# ARM2toARM3Adapter.net
KiCad netlist of a schematic drawn in Altium Designer
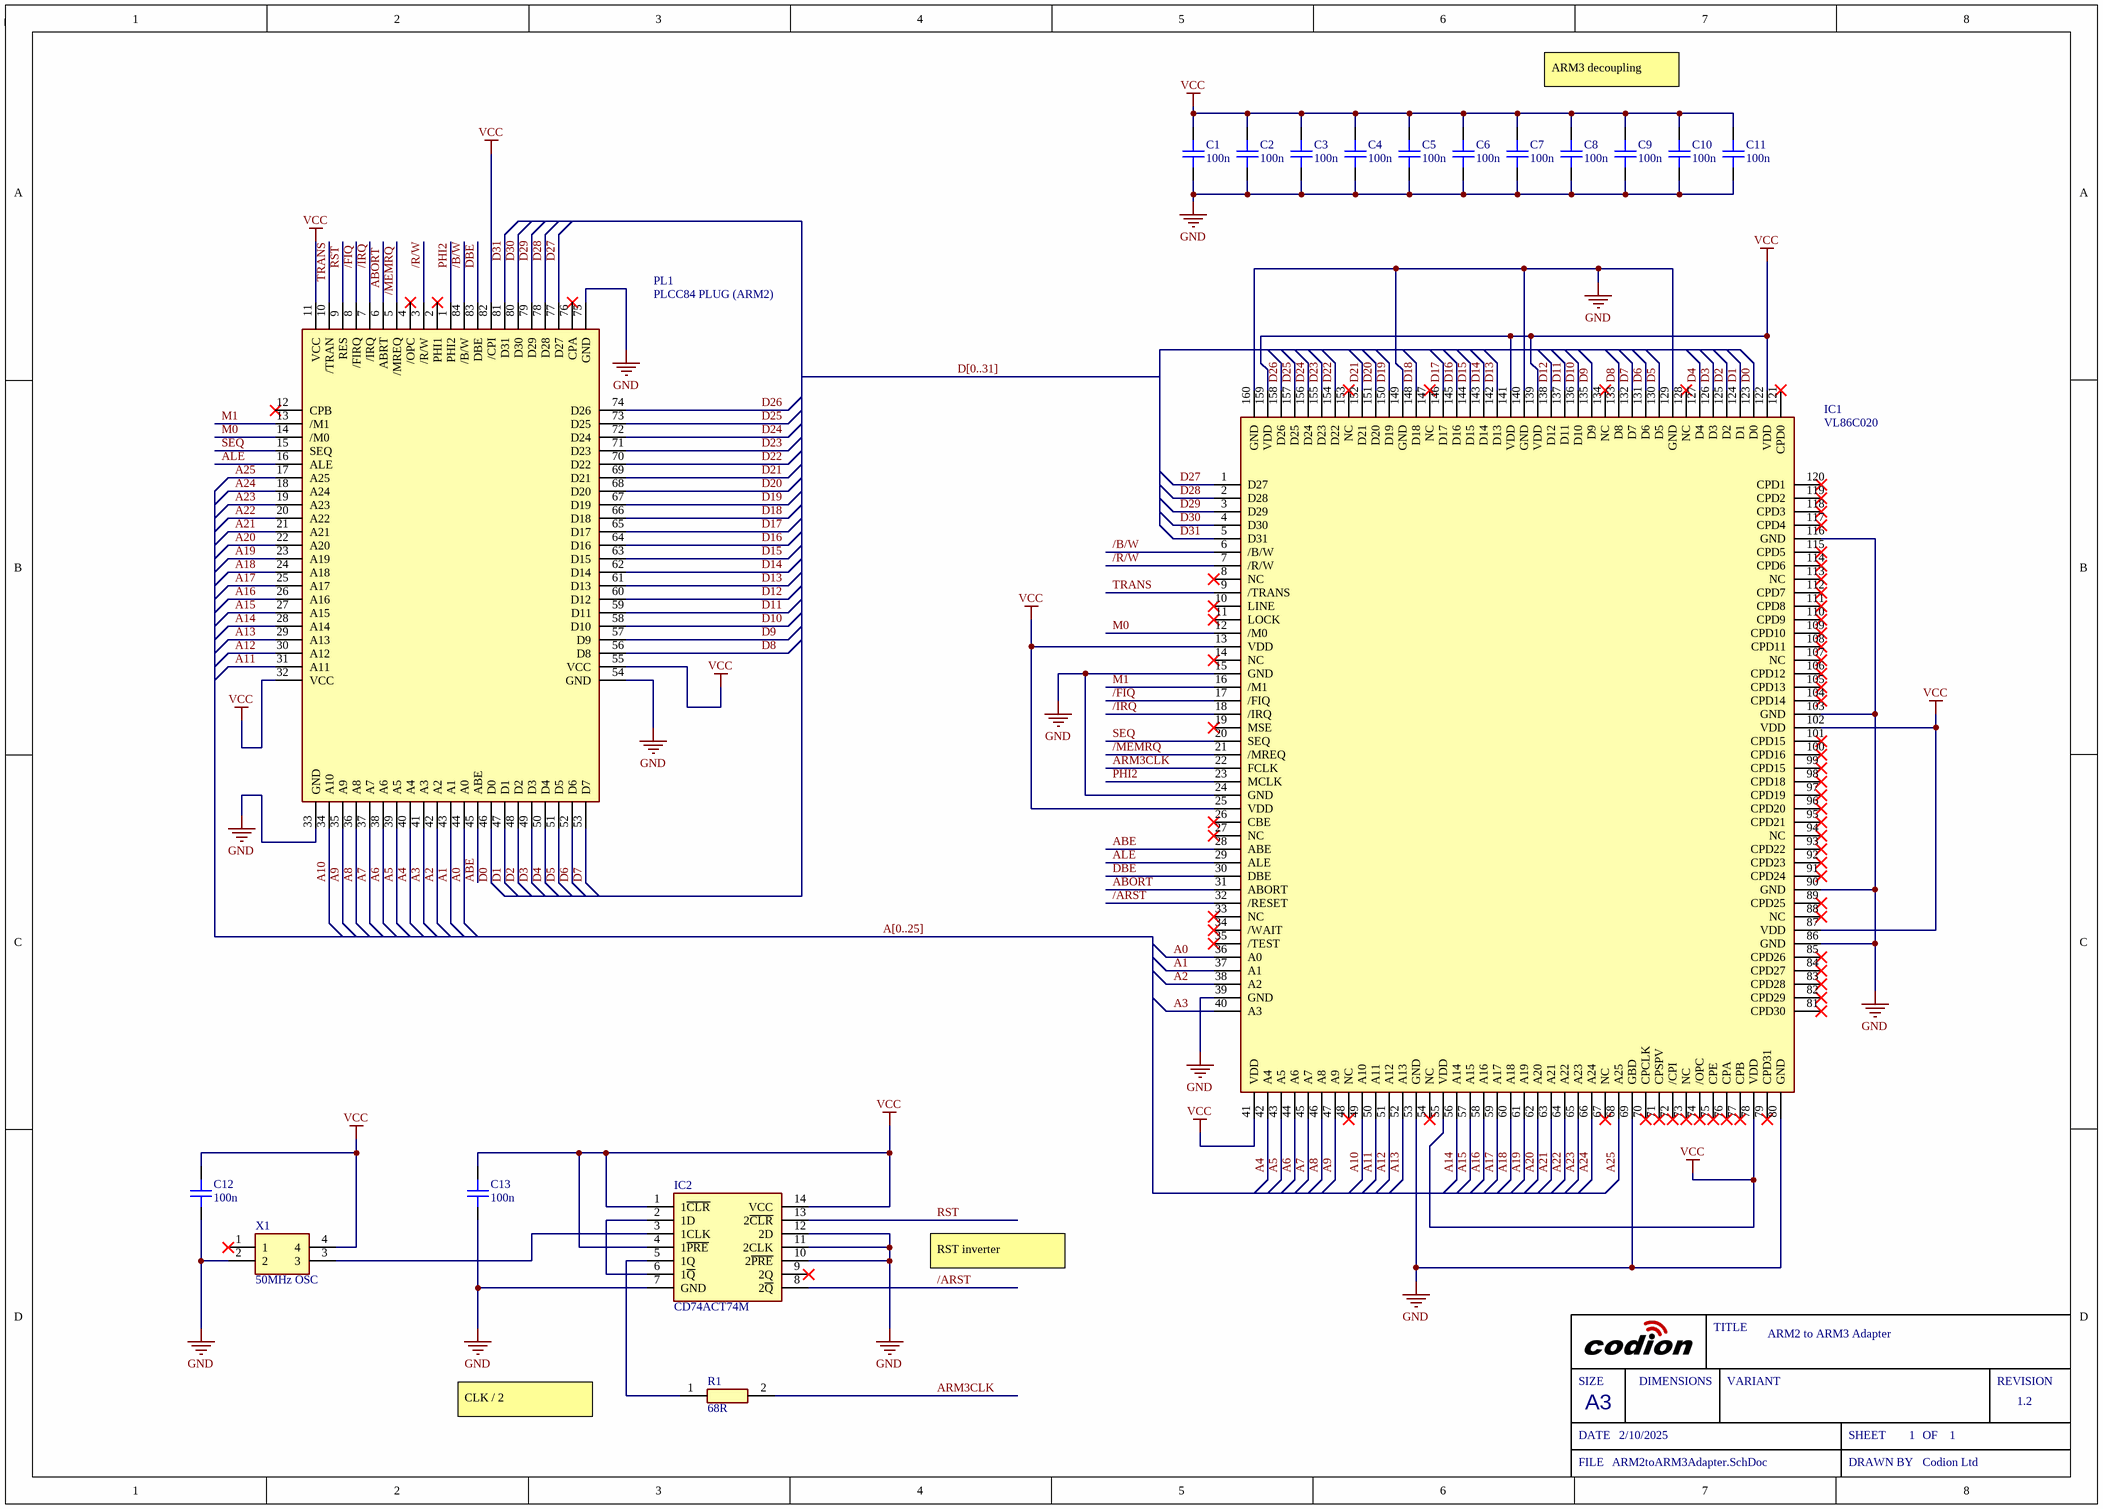
[diagram p0: ARM2toARM3Adapter.SchDoc]

(export (version "E")
  (design (tool "Eeschema 10.0.6"))
  (components
    (comp (ref "C1")
      (value "100n")
      (footprint "CAPC1608L")
      (description "CAP 100nF, 0603, 50V, X7R, 10%")
      (fields
        (field (name "DISTRIBUTOR1 PART NO") "CL10B104KB8NNNC")
        (field (name "DISTRIBUTOR2 PART NO") "311-1344-2-ND")
      )
      (libsource (lib "MCP1002_RevC") (part "CAP_100n_0603_50V_0"))
    )
    (comp (ref "C2")
      (value "100n")
      (footprint "CAPC1608L")
      (description "CAP 100nF, 0603, 50V, X7R, 10%")
      (fields
        (field (name "DISTRIBUTOR1 PART NO") "CL10B104KB8NNNC")
        (field (name "DISTRIBUTOR2 PART NO") "311-1344-2-ND")
      )
      (libsource (lib "MCP1002_RevC") (part "CAP_100n_0603_50V_0"))
    )
    (comp (ref "C3")
      (value "100n")
      (footprint "CAPC1608L")
      (description "CAP 100nF, 0603, 50V, X7R, 10%")
      (fields
        (field (name "DISTRIBUTOR1 PART NO") "CL10B104KB8NNNC")
        (field (name "DISTRIBUTOR2 PART NO") "311-1344-2-ND")
      )
      (libsource (lib "MCP1002_RevC") (part "CAP_100n_0603_50V_0"))
    )
    (comp (ref "C4")
      (value "100n")
      (footprint "CAPC1608L")
      (description "CAP 100nF, 0603, 50V, X7R, 10%")
      (fields
        (field (name "DISTRIBUTOR1 PART NO") "CL10B104KB8NNNC")
        (field (name "DISTRIBUTOR2 PART NO") "311-1344-2-ND")
      )
      (libsource (lib "MCP1002_RevC") (part "CAP_100n_0603_50V_0"))
    )
    (comp (ref "C5")
      (value "100n")
      (footprint "CAPC1608L")
      (description "CAP 100nF, 0603, 50V, X7R, 10%")
      (fields
        (field (name "DISTRIBUTOR1 PART NO") "CL10B104KB8NNNC")
        (field (name "DISTRIBUTOR2 PART NO") "311-1344-2-ND")
      )
      (libsource (lib "MCP1002_RevC") (part "CAP_100n_0603_50V_0"))
    )
    (comp (ref "C6")
      (value "100n")
      (footprint "CAPC1608L")
      (description "CAP 100nF, 0603, 50V, X7R, 10%")
      (fields
        (field (name "DISTRIBUTOR1 PART NO") "CL10B104KB8NNNC")
        (field (name "DISTRIBUTOR2 PART NO") "311-1344-2-ND")
      )
      (libsource (lib "MCP1002_RevC") (part "CAP_100n_0603_50V_0"))
    )
    (comp (ref "C7")
      (value "100n")
      (footprint "CAPC1608L")
      (description "CAP 100nF, 0603, 50V, X7R, 10%")
      (fields
        (field (name "DISTRIBUTOR1 PART NO") "CL10B104KB8NNNC")
        (field (name "DISTRIBUTOR2 PART NO") "311-1344-2-ND")
      )
      (libsource (lib "MCP1002_RevC") (part "CAP_100n_0603_50V_0"))
    )
    (comp (ref "C8")
      (value "100n")
      (footprint "CAPC1608L")
      (description "CAP 100nF, 0603, 50V, X7R, 10%")
      (fields
        (field (name "DISTRIBUTOR1 PART NO") "CL10B104KB8NNNC")
        (field (name "DISTRIBUTOR2 PART NO") "311-1344-2-ND")
      )
      (libsource (lib "MCP1002_RevC") (part "CAP_100n_0603_50V_0"))
    )
    (comp (ref "C9")
      (value "100n")
      (footprint "CAPC1608L")
      (description "CAP 100nF, 0603, 50V, X7R, 10%")
      (fields
        (field (name "DISTRIBUTOR1 PART NO") "CL10B104KB8NNNC")
        (field (name "DISTRIBUTOR2 PART NO") "311-1344-2-ND")
      )
      (libsource (lib "MCP1002_RevC") (part "CAP_100n_0603_50V_0"))
    )
    (comp (ref "C10")
      (value "100n")
      (footprint "CAPC1608L")
      (description "CAP 100nF, 0603, 50V, X7R, 10%")
      (fields
        (field (name "DISTRIBUTOR1 PART NO") "CL10B104KB8NNNC")
        (field (name "DISTRIBUTOR2 PART NO") "311-1344-2-ND")
      )
      (libsource (lib "MCP1002_RevC") (part "CAP_100n_0603_50V_0"))
    )
    (comp (ref "C11")
      (value "100n")
      (footprint "CAPC1608L")
      (description "CAP 100nF, 0603, 50V, X7R, 10%")
      (fields
        (field (name "DISTRIBUTOR1 PART NO") "CL10B104KB8NNNC")
        (field (name "DISTRIBUTOR2 PART NO") "311-1344-2-ND")
      )
      (libsource (lib "MCP1002_RevC") (part "CAP_100n_0603_50V_0"))
    )
    (comp (ref "C12")
      (value "100n")
      (footprint "CAPC1608L")
      (description "CAP 100nF, 0603, 50V, X7R, 10%")
      (fields
        (field (name "DISTRIBUTOR1 PART NO") "CL10B104KB8NNNC")
        (field (name "DISTRIBUTOR2 PART NO") "311-1344-2-ND")
      )
      (libsource (lib "MCP1002_RevC") (part "CAP_100n_0603_50V_0"))
    )
    (comp (ref "C13")
      (value "100n")
      (footprint "CAPC1608L")
      (description "CAP 100nF, 0603, 50V, X7R, 10%")
      (fields
        (field (name "DISTRIBUTOR1 PART NO") "CL10B104KB8NNNC")
        (field (name "DISTRIBUTOR2 PART NO") "311-1344-2-ND")
      )
      (libsource (lib "MCP1002_RevC") (part "CAP_100n_0603_50V_0"))
    )
    (comp (ref "IC1")
      (value "VL86C020")
      (footprint "SamacSys:QFP65P3120X3120X407-160N")
      (description "ARM3")
      (fields (field (name "MANUFACTURER_PART_NUMBER") "VL86C)20"))
      (libsource (lib "*") (part "SAA7146AH_V4,557"))
    )
    (comp (ref "IC2")
      (value "CD74ACT74M")
      (footprint "SamacSys:SOIC127P600X175-14N")
      (description "Integrated Circuit")
      (fields (field (name "MOUSER PART NUMBER") "595-CD74ACT74M"))
      (libsource (lib "*") (part "CD74ACT74M"))
    )
    (comp (ref "PL1")
      (value "PLCC84 PLUG (ARM2)")
      (footprint "PLCC84_PLUG")
      (description "PLCC84 Plug")
      (fields (field (name "MANUFACTURER_PART_NUMBER") "W9328"))
      (libsource (lib "ARM2toARM3Adapter") (part "PLCC84_PLUG_ARM2"))
    )
    (comp (ref "R1")
      (value "68R")
      (footprint "SamacSys:RESC2012X50N")
      (description "68R Resistor")
      (fields
        (field (name "MANUFACTURER_PART_NUMBER") "CRCW080568R0FKEA")
        (field (name "MOUSER PART NUMBER") "71-CRCW080568R0FKEA")
      )
      (libsource (lib "*") (part "CRCW080568R0FKEA"))
    )
    (comp (ref "X1")
      (value "50MHz OSC")
      (footprint "SamacSys:DIPS762W56P1524L1778H241Q4N")
      (fields
        (field (name "MANUFACTURER_PART_NUMBER") "1107741")
        (field (name "MOUSER PART NUMBER") "535-1107741")
      )
      (libsource (lib "*") (part "1107741"))
    )
  )
  (nets
    (net (code "1") (name "/A0") (class "Default")
      (node (ref "IC1") (pin "36") (pinfunction "A0_36") (pintype "passive"))
      (node (ref "PL1") (pin "44") (pinfunction "A0_44") (pintype "passive"))
    )
    (net (code "2") (name "/A1") (class "Default")
      (node (ref "IC1") (pin "37") (pinfunction "A1_37") (pintype "passive"))
      (node (ref "PL1") (pin "43") (pinfunction "A1_43") (pintype "passive"))
    )
    (net (code "3") (name "/A2") (class "Default")
      (node (ref "IC1") (pin "38") (pinfunction "A2_38") (pintype "passive"))
      (node (ref "PL1") (pin "42") (pinfunction "A2_42") (pintype "passive"))
    )
    (net (code "4") (name "/A3") (class "Default")
      (node (ref "IC1") (pin "40") (pinfunction "A3_40") (pintype "passive"))
      (node (ref "PL1") (pin "41") (pinfunction "A3_41") (pintype "passive"))
    )
    (net (code "5") (name "/A4") (class "Default")
      (node (ref "IC1") (pin "42") (pinfunction "A4_42") (pintype "passive"))
      (node (ref "PL1") (pin "40") (pinfunction "A4_40") (pintype "passive"))
    )
    (net (code "6") (name "/A5") (class "Default")
      (node (ref "IC1") (pin "43") (pinfunction "A5_43") (pintype "passive"))
      (node (ref "PL1") (pin "39") (pinfunction "A5_39") (pintype "passive"))
    )
    (net (code "7") (name "/A6") (class "Default")
      (node (ref "IC1") (pin "44") (pinfunction "A6_44") (pintype "passive"))
      (node (ref "PL1") (pin "38") (pinfunction "A6_38") (pintype "passive"))
    )
    (net (code "8") (name "/A7") (class "Default")
      (node (ref "IC1") (pin "45") (pinfunction "A7_45") (pintype "passive"))
      (node (ref "PL1") (pin "37") (pinfunction "A7_37") (pintype "passive"))
    )
    (net (code "9") (name "/A8") (class "Default")
      (node (ref "IC1") (pin "46") (pinfunction "A8_46") (pintype "passive"))
      (node (ref "PL1") (pin "36") (pinfunction "A8_36") (pintype "passive"))
    )
    (net (code "10") (name "/A9") (class "Default")
      (node (ref "IC1") (pin "47") (pinfunction "A9_47") (pintype "passive"))
      (node (ref "PL1") (pin "35") (pinfunction "A9_35") (pintype "passive"))
    )
    (net (code "11") (name "/A10") (class "Default")
      (node (ref "IC1") (pin "49") (pinfunction "A10_49") (pintype "passive"))
      (node (ref "PL1") (pin "34") (pinfunction "A10_34") (pintype "passive"))
    )
    (net (code "12") (name "/A11") (class "Default")
      (node (ref "IC1") (pin "50") (pinfunction "A11_50") (pintype "passive"))
      (node (ref "PL1") (pin "31") (pinfunction "A11_31") (pintype "passive"))
    )
    (net (code "13") (name "/A12") (class "Default")
      (node (ref "IC1") (pin "51") (pinfunction "A12_51") (pintype "passive"))
      (node (ref "PL1") (pin "30") (pinfunction "A12_30") (pintype "passive"))
    )
    (net (code "14") (name "/A13") (class "Default")
      (node (ref "IC1") (pin "52") (pinfunction "A13_52") (pintype "passive"))
      (node (ref "PL1") (pin "29") (pinfunction "A13_29") (pintype "passive"))
    )
    (net (code "15") (name "/A14") (class "Default")
      (node (ref "IC1") (pin "56") (pinfunction "A14_56") (pintype "passive"))
      (node (ref "PL1") (pin "28") (pinfunction "A14_28") (pintype "passive"))
    )
    (net (code "16") (name "/A15") (class "Default")
      (node (ref "IC1") (pin "57") (pinfunction "A15_57") (pintype "passive"))
      (node (ref "PL1") (pin "27") (pinfunction "A15_27") (pintype "passive"))
    )
    (net (code "17") (name "/A16") (class "Default")
      (node (ref "IC1") (pin "58") (pinfunction "A16_58") (pintype "passive"))
      (node (ref "PL1") (pin "26") (pinfunction "A16_26") (pintype "passive"))
    )
    (net (code "18") (name "/A17") (class "Default")
      (node (ref "IC1") (pin "59") (pinfunction "A17_59") (pintype "passive"))
      (node (ref "PL1") (pin "25") (pinfunction "A17_25") (pintype "passive"))
    )
    (net (code "19") (name "/A18") (class "Default")
      (node (ref "IC1") (pin "60") (pinfunction "A18_60") (pintype "passive"))
      (node (ref "PL1") (pin "24") (pinfunction "A18_24") (pintype "passive"))
    )
    (net (code "20") (name "/A19") (class "Default")
      (node (ref "IC1") (pin "61") (pinfunction "A19_61") (pintype "passive"))
      (node (ref "PL1") (pin "23") (pinfunction "A19_23") (pintype "passive"))
    )
    (net (code "21") (name "/A20") (class "Default")
      (node (ref "IC1") (pin "62") (pinfunction "A20_62") (pintype "passive"))
      (node (ref "PL1") (pin "22") (pinfunction "A20_22") (pintype "passive"))
    )
    (net (code "22") (name "/A21") (class "Default")
      (node (ref "IC1") (pin "63") (pinfunction "A21_63") (pintype "passive"))
      (node (ref "PL1") (pin "21") (pinfunction "A21_21") (pintype "passive"))
    )
    (net (code "23") (name "/A22") (class "Default")
      (node (ref "IC1") (pin "64") (pinfunction "A22_64") (pintype "passive"))
      (node (ref "PL1") (pin "20") (pinfunction "A22_20") (pintype "passive"))
    )
    (net (code "24") (name "/A23") (class "Default")
      (node (ref "IC1") (pin "65") (pinfunction "A23_65") (pintype "passive"))
      (node (ref "PL1") (pin "19") (pinfunction "A23_19") (pintype "passive"))
    )
    (net (code "25") (name "/A24") (class "Default")
      (node (ref "IC1") (pin "66") (pinfunction "A24_66") (pintype "passive"))
      (node (ref "PL1") (pin "18") (pinfunction "A24_18") (pintype "passive"))
    )
    (net (code "26") (name "/A25") (class "Default")
      (node (ref "IC1") (pin "68") (pinfunction "A25_68") (pintype "passive"))
      (node (ref "PL1") (pin "17") (pinfunction "A25_17") (pintype "passive"))
    )
    (net (code "27") (name "/ABE") (class "Default")
      (node (ref "IC1") (pin "28") (pinfunction "ABE_28") (pintype "passive"))
      (node (ref "PL1") (pin "45") (pinfunction "ABE_45") (pintype "passive"))
    )
    (net (code "28") (name "/ABORT") (class "Default")
      (node (ref "IC1") (pin "31") (pinfunction "ABORT_31") (pintype "passive"))
      (node (ref "PL1") (pin "6") (pinfunction "ABRT_6") (pintype "passive"))
    )
    (net (code "29") (name "/ALE") (class "Default")
      (node (ref "IC1") (pin "29") (pinfunction "ALE_29") (pintype "passive"))
      (node (ref "PL1") (pin "16") (pinfunction "ALE_16") (pintype "passive"))
    )
    (net (code "30") (name "/ARM3CLK") (class "Default")
      (node (ref "IC1") (pin "22") (pinfunction "FCLK_22") (pintype "passive"))
      (node (ref "R1") (pin "2") (pinfunction "2_2") (pintype "passive"))
    )
    (net (code "32") (name "/D0") (class "Default")
      (node (ref "IC1") (pin "123") (pinfunction "D0_123") (pintype "passive"))
      (node (ref "PL1") (pin "46") (pinfunction "D0_46") (pintype "passive"))
    )
    (net (code "33") (name "/D1") (class "Default")
      (node (ref "IC1") (pin "124") (pinfunction "D1_124") (pintype "passive"))
      (node (ref "PL1") (pin "47") (pinfunction "D1_47") (pintype "passive"))
    )
    (net (code "34") (name "/D2") (class "Default")
      (node (ref "IC1") (pin "125") (pinfunction "D2_125") (pintype "passive"))
      (node (ref "PL1") (pin "48") (pinfunction "D2_48") (pintype "passive"))
    )
    (net (code "35") (name "/D3") (class "Default")
      (node (ref "IC1") (pin "126") (pinfunction "D3_126") (pintype "passive"))
      (node (ref "PL1") (pin "49") (pinfunction "D3_49") (pintype "passive"))
    )
    (net (code "36") (name "/D4") (class "Default")
      (node (ref "IC1") (pin "127") (pinfunction "D4_127") (pintype "passive"))
      (node (ref "PL1") (pin "50") (pinfunction "D4_50") (pintype "passive"))
    )
    (net (code "37") (name "/D5") (class "Default")
      (node (ref "IC1") (pin "130") (pinfunction "D5_130") (pintype "passive"))
      (node (ref "PL1") (pin "51") (pinfunction "D5_51") (pintype "passive"))
    )
    (net (code "38") (name "/D6") (class "Default")
      (node (ref "IC1") (pin "131") (pinfunction "D6_131") (pintype "passive"))
      (node (ref "PL1") (pin "52") (pinfunction "D6_52") (pintype "passive"))
    )
    (net (code "39") (name "/D7") (class "Default")
      (node (ref "IC1") (pin "132") (pinfunction "D7_132") (pintype "passive"))
      (node (ref "PL1") (pin "53") (pinfunction "D7_53") (pintype "passive"))
    )
    (net (code "40") (name "/D8") (class "Default")
      (node (ref "IC1") (pin "133") (pinfunction "D8_133") (pintype "passive"))
      (node (ref "PL1") (pin "56") (pinfunction "D8_56") (pintype "passive"))
    )
    (net (code "41") (name "/D9") (class "Default")
      (node (ref "IC1") (pin "135") (pinfunction "D9_135") (pintype "passive"))
      (node (ref "PL1") (pin "57") (pinfunction "D9_57") (pintype "passive"))
    )
    (net (code "42") (name "/D10") (class "Default")
      (node (ref "IC1") (pin "136") (pinfunction "D10_136") (pintype "passive"))
      (node (ref "PL1") (pin "58") (pinfunction "D10_58") (pintype "passive"))
    )
    (net (code "43") (name "/D11") (class "Default")
      (node (ref "IC1") (pin "137") (pinfunction "D11_137") (pintype "passive"))
      (node (ref "PL1") (pin "59") (pinfunction "D11_59") (pintype "passive"))
    )
    (net (code "44") (name "/D12") (class "Default")
      (node (ref "IC1") (pin "138") (pinfunction "D12_138") (pintype "passive"))
      (node (ref "PL1") (pin "60") (pinfunction "D12_60") (pintype "passive"))
    )
    (net (code "45") (name "/D13") (class "Default")
      (node (ref "IC1") (pin "142") (pinfunction "D13_142") (pintype "passive"))
      (node (ref "PL1") (pin "61") (pinfunction "D13_61") (pintype "passive"))
    )
    (net (code "46") (name "/D14") (class "Default")
      (node (ref "IC1") (pin "143") (pinfunction "D14_143") (pintype "passive"))
      (node (ref "PL1") (pin "62") (pinfunction "D14_62") (pintype "passive"))
    )
    (net (code "47") (name "/D15") (class "Default")
      (node (ref "IC1") (pin "144") (pinfunction "D15_144") (pintype "passive"))
      (node (ref "PL1") (pin "63") (pinfunction "D15_63") (pintype "passive"))
    )
    (net (code "48") (name "/D16") (class "Default")
      (node (ref "IC1") (pin "145") (pinfunction "D16_145") (pintype "passive"))
      (node (ref "PL1") (pin "64") (pinfunction "D16_64") (pintype "passive"))
    )
    (net (code "49") (name "/D17") (class "Default")
      (node (ref "IC1") (pin "146") (pinfunction "D17_146") (pintype "passive"))
      (node (ref "PL1") (pin "65") (pinfunction "D17_65") (pintype "passive"))
    )
    (net (code "50") (name "/D18") (class "Default")
      (node (ref "IC1") (pin "148") (pinfunction "D18_148") (pintype "passive"))
      (node (ref "PL1") (pin "66") (pinfunction "D18_66") (pintype "passive"))
    )
    (net (code "51") (name "/D19") (class "Default")
      (node (ref "IC1") (pin "150") (pinfunction "D19_150") (pintype "passive"))
      (node (ref "PL1") (pin "67") (pinfunction "D19_67") (pintype "passive"))
    )
    (net (code "52") (name "/D20") (class "Default")
      (node (ref "IC1") (pin "151") (pinfunction "D20_151") (pintype "passive"))
      (node (ref "PL1") (pin "68") (pinfunction "D20_68") (pintype "passive"))
    )
    (net (code "53") (name "/D21") (class "Default")
      (node (ref "IC1") (pin "152") (pinfunction "D21_152") (pintype "passive"))
      (node (ref "PL1") (pin "69") (pinfunction "D21_69") (pintype "passive"))
    )
    (net (code "54") (name "/D22") (class "Default")
      (node (ref "IC1") (pin "154") (pinfunction "D22_154") (pintype "passive"))
      (node (ref "PL1") (pin "70") (pinfunction "D22_70") (pintype "passive"))
    )
    (net (code "55") (name "/D23") (class "Default")
      (node (ref "IC1") (pin "155") (pinfunction "D23_155") (pintype "passive"))
      (node (ref "PL1") (pin "71") (pinfunction "D23_71") (pintype "passive"))
    )
    (net (code "56") (name "/D24") (class "Default")
      (node (ref "IC1") (pin "156") (pinfunction "D24_156") (pintype "passive"))
      (node (ref "PL1") (pin "72") (pinfunction "D24_72") (pintype "passive"))
    )
    (net (code "57") (name "/D25") (class "Default")
      (node (ref "IC1") (pin "157") (pinfunction "D25_157") (pintype "passive"))
      (node (ref "PL1") (pin "73") (pinfunction "D25_73") (pintype "passive"))
    )
    (net (code "58") (name "/D26") (class "Default")
      (node (ref "IC1") (pin "158") (pinfunction "D26_158") (pintype "passive"))
      (node (ref "PL1") (pin "74") (pinfunction "D26_74") (pintype "passive"))
    )
    (net (code "59") (name "/D27") (class "Default")
      (node (ref "IC1") (pin "1") (pinfunction "D27_1") (pintype "passive"))
      (node (ref "PL1") (pin "77") (pinfunction "D27_77") (pintype "passive"))
    )
    (net (code "60") (name "/D28") (class "Default")
      (node (ref "IC1") (pin "2") (pinfunction "D28_2") (pintype "passive"))
      (node (ref "PL1") (pin "78") (pinfunction "D28_78") (pintype "passive"))
    )
    (net (code "61") (name "/D29") (class "Default")
      (node (ref "IC1") (pin "3") (pinfunction "D29_3") (pintype "passive"))
      (node (ref "PL1") (pin "79") (pinfunction "D29_79") (pintype "passive"))
    )
    (net (code "62") (name "/D30") (class "Default")
      (node (ref "IC1") (pin "4") (pinfunction "D30_4") (pintype "passive"))
      (node (ref "PL1") (pin "80") (pinfunction "D30_80") (pintype "passive"))
    )
    (net (code "63") (name "/D31") (class "Default")
      (node (ref "IC1") (pin "5") (pinfunction "D31_5") (pintype "passive"))
      (node (ref "PL1") (pin "81") (pinfunction "D31_81") (pintype "passive"))
    )
    (net (code "64") (name "/DBE") (class "Default")
      (node (ref "IC1") (pin "30") (pinfunction "DBE_30") (pintype "passive"))
      (node (ref "PL1") (pin "83") (pinfunction "DBE_83") (pintype "passive"))
    )
    (net (code "66") (name "/M0") (class "Default")
      (node (ref "IC1") (pin "12") (pinfunction "/M0_12") (pintype "passive"))
      (node (ref "PL1") (pin "14") (pinfunction "/M0_14") (pintype "passive"))
    )
    (net (code "67") (name "/M1") (class "Default")
      (node (ref "IC1") (pin "16") (pinfunction "/M1_16") (pintype "passive"))
      (node (ref "PL1") (pin "13") (pinfunction "/M1_13") (pintype "passive"))
    )
    (net (code "68") (name "/PHI2") (class "Default")
      (node (ref "IC1") (pin "23") (pinfunction "MCLK_23") (pintype "passive"))
      (node (ref "PL1") (pin "1") (pinfunction "PHI2_1") (pintype "passive"))
    )
    (net (code "69") (name "/RST") (class "Default")
      (node (ref "IC2") (pin "13") (pinfunction "2~{CLR}_13") (pintype "passive"))
      (node (ref "PL1") (pin "9") (pinfunction "RES_9") (pintype "passive"))
    )
    (net (code "70") (name "/SEQ") (class "Default")
      (node (ref "IC1") (pin "20") (pinfunction "SEQ_20") (pintype "passive"))
      (node (ref "PL1") (pin "15") (pinfunction "SEQ_15") (pintype "passive"))
    )
    (net (code "71") (name "/TRANS") (class "Default")
      (node (ref "IC1") (pin "9") (pinfunction "/TRANS_9") (pintype "passive"))
      (node (ref "PL1") (pin "10") (pinfunction "/TRAN_10") (pintype "passive"))
    )
    (net (code "72") (name "/{slash}ARST") (class "Default")
      (node (ref "IC1") (pin "32") (pinfunction "/RESET_32") (pintype "passive"))
      (node (ref "IC2") (pin "8") (pinfunction "2~{Q}_8") (pintype "passive"))
    )
    (net (code "73") (name "/{slash}B{slash}W") (class "Default")
      (node (ref "IC1") (pin "6") (pinfunction "/B/W_6") (pintype "passive"))
      (node (ref "PL1") (pin "84") (pinfunction "/B/W_84") (pintype "passive"))
    )
    (net (code "74") (name "/{slash}FIQ") (class "Default")
      (node (ref "IC1") (pin "17") (pinfunction "/FIQ_17") (pintype "passive"))
      (node (ref "PL1") (pin "8") (pinfunction "/FIRQ_8") (pintype "passive"))
    )
    (net (code "75") (name "/{slash}IRQ") (class "Default")
      (node (ref "IC1") (pin "18") (pinfunction "/IRQ_18") (pintype "passive"))
      (node (ref "PL1") (pin "7") (pinfunction "/IRQ_7") (pintype "passive"))
    )
    (net (code "76") (name "/{slash}MEMRQ") (class "Default")
      (node (ref "IC1") (pin "21") (pinfunction "/MREQ_21") (pintype "passive"))
      (node (ref "PL1") (pin "5") (pinfunction "/MREQ_5") (pintype "passive"))
    )
    (net (code "77") (name "/{slash}R{slash}W") (class "Default")
      (node (ref "IC1") (pin "7") (pinfunction "/R/W_7") (pintype "passive"))
      (node (ref "PL1") (pin "3") (pinfunction "/R/W_3") (pintype "passive"))
    )
    (net (code "78") (name "GND") (class "Default")
      (node (ref "C1") (pin "1") (pintype "passive"))
      (node (ref "C10") (pin "1") (pintype "passive"))
      (node (ref "C11") (pin "1") (pintype "passive"))
      (node (ref "C12") (pin "1") (pintype "passive"))
      (node (ref "C13") (pin "1") (pintype "passive"))
      (node (ref "C2") (pin "1") (pintype "passive"))
      (node (ref "C3") (pin "1") (pintype "passive"))
      (node (ref "C4") (pin "1") (pintype "passive"))
      (node (ref "C5") (pin "1") (pintype "passive"))
      (node (ref "C6") (pin "1") (pintype "passive"))
      (node (ref "C7") (pin "1") (pintype "passive"))
      (node (ref "C8") (pin "1") (pintype "passive"))
      (node (ref "C9") (pin "1") (pintype "passive"))
      (node (ref "IC1") (pin "103") (pinfunction "GND_103") (pintype "passive"))
      (node (ref "IC1") (pin "116") (pinfunction "GND_116") (pintype "passive"))
      (node (ref "IC1") (pin "129") (pinfunction "GND_129") (pintype "passive"))
      (node (ref "IC1") (pin "140") (pinfunction "GND_140") (pintype "passive"))
      (node (ref "IC1") (pin "149") (pinfunction "GND_149") (pintype "passive"))
      (node (ref "IC1") (pin "15") (pinfunction "GND_15") (pintype "passive"))
      (node (ref "IC1") (pin "160") (pinfunction "GND_160") (pintype "passive"))
      (node (ref "IC1") (pin "24") (pinfunction "GND_24") (pintype "passive"))
      (node (ref "IC1") (pin "39") (pinfunction "GND_39") (pintype "passive"))
      (node (ref "IC1") (pin "53") (pinfunction "GND_53") (pintype "passive"))
      (node (ref "IC1") (pin "69") (pinfunction "GBD_69") (pintype "passive"))
      (node (ref "IC1") (pin "80") (pinfunction "GND_80") (pintype "passive"))
      (node (ref "IC1") (pin "86") (pinfunction "GND_86") (pintype "passive"))
      (node (ref "IC1") (pin "90") (pinfunction "GND_90") (pintype "passive"))
      (node (ref "IC2") (pin "10") (pinfunction "2~{PRE}_10") (pintype "passive"))
      (node (ref "IC2") (pin "11") (pinfunction "2CLK_11") (pintype "passive"))
      (node (ref "IC2") (pin "12") (pinfunction "2D_12") (pintype "passive"))
      (node (ref "IC2") (pin "7") (pinfunction "GND_7") (pintype "passive"))
      (node (ref "PL1") (pin "33") (pinfunction "GND_33") (pintype "passive"))
      (node (ref "PL1") (pin "54") (pinfunction "GND_54") (pintype "passive"))
      (node (ref "PL1") (pin "75") (pinfunction "GND_75") (pintype "passive"))
      (node (ref "X1") (pin "2") (pinfunction "2_2") (pintype "passive"))
    )
    (net (code "79") (name "Net-(IC2-1CLK)") (class "Default")
      (node (ref "IC2") (pin "3") (pinfunction "1CLK_3") (pintype "passive"))
      (node (ref "X1") (pin "3") (pinfunction "3_3") (pintype "passive"))
    )
    (net (code "80") (name "Net-(IC2-1D)") (class "Default")
      (node (ref "IC2") (pin "2") (pinfunction "1D_2") (pintype "passive"))
      (node (ref "IC2") (pin "6") (pinfunction "1~{Q}_6") (pintype "passive"))
    )
    (net (code "81") (name "Net-(IC2-1Q)") (class "Default")
      (node (ref "IC2") (pin "5") (pinfunction "1Q_5") (pintype "passive"))
      (node (ref "R1") (pin "1") (pinfunction "1_1") (pintype "passive"))
    )
    (net (code "82") (name "VCC") (class "Default")
      (node (ref "C1") (pin "2") (pintype "passive"))
      (node (ref "C10") (pin "2") (pintype "passive"))
      (node (ref "C11") (pin "2") (pintype "passive"))
      (node (ref "C12") (pin "2") (pintype "passive"))
      (node (ref "C13") (pin "2") (pintype "passive"))
      (node (ref "C2") (pin "2") (pintype "passive"))
      (node (ref "C3") (pin "2") (pintype "passive"))
      (node (ref "C4") (pin "2") (pintype "passive"))
      (node (ref "C5") (pin "2") (pintype "passive"))
      (node (ref "C6") (pin "2") (pintype "passive"))
      (node (ref "C7") (pin "2") (pintype "passive"))
      (node (ref "C8") (pin "2") (pintype "passive"))
      (node (ref "C9") (pin "2") (pintype "passive"))
      (node (ref "IC1") (pin "102") (pinfunction "VDD_102") (pintype "passive"))
      (node (ref "IC1") (pin "122") (pinfunction "VDD_122") (pintype "passive"))
      (node (ref "IC1") (pin "13") (pinfunction "VDD_13") (pintype "passive"))
      (node (ref "IC1") (pin "139") (pinfunction "VDD_139") (pintype "passive"))
      (node (ref "IC1") (pin "141") (pinfunction "VDD_141") (pintype "passive"))
      (node (ref "IC1") (pin "159") (pinfunction "VDD_159") (pintype "passive"))
      (node (ref "IC1") (pin "25") (pinfunction "VDD_25") (pintype "passive"))
      (node (ref "IC1") (pin "41") (pinfunction "VDD_41") (pintype "passive"))
      (node (ref "IC1") (pin "55") (pinfunction "VDD_55") (pintype "passive"))
      (node (ref "IC1") (pin "78") (pinfunction "VDD_78") (pintype "passive"))
      (node (ref "IC1") (pin "87") (pinfunction "VDD_87") (pintype "passive"))
      (node (ref "IC2") (pin "1") (pinfunction "1~{CLR}_1") (pintype "passive"))
      (node (ref "IC2") (pin "14") (pinfunction "VCC_14") (pintype "passive"))
      (node (ref "IC2") (pin "4") (pinfunction "1~{PRE}_4") (pintype "passive"))
      (node (ref "PL1") (pin "11") (pinfunction "VCC_11") (pintype "passive"))
      (node (ref "PL1") (pin "32") (pinfunction "VCC_32") (pintype "passive"))
      (node (ref "PL1") (pin "55") (pinfunction "VCC_55") (pintype "passive"))
      (node (ref "PL1") (pin "82") (pinfunction "/CPI_82") (pintype "passive"))
      (node (ref "X1") (pin "4") (pinfunction "4_4") (pintype "passive"))
    )
    (net (code "83") (name "unconnected-(IC1-CBE-Pad26)") (class "Default")
      (node (ref "IC1") (pin "26") (pinfunction "CBE_26") (pintype "passive+no_connect"))
    )
    (net (code "84") (name "unconnected-(IC1-CPA-Pad76)") (class "Default")
      (node (ref "IC1") (pin "76") (pinfunction "CPA_76") (pintype "passive+no_connect"))
    )
    (net (code "85") (name "unconnected-(IC1-CPB-Pad77)") (class "Default")
      (node (ref "IC1") (pin "77") (pinfunction "CPB_77") (pintype "passive+no_connect"))
    )
    (net (code "86") (name "unconnected-(IC1-CPCLK-Pad70)") (class "Default")
      (node (ref "IC1") (pin "70") (pinfunction "CPCLK_70") (pintype "passive+no_connect"))
    )
    (net (code "87") (name "unconnected-(IC1-CPD0-Pad121)") (class "Default")
      (node (ref "IC1") (pin "121") (pinfunction "CPD0_121") (pintype "passive+no_connect"))
    )
    (net (code "88") (name "unconnected-(IC1-CPD1-Pad120)") (class "Default")
      (node (ref "IC1") (pin "120") (pinfunction "CPD1_120") (pintype "passive+no_connect"))
    )
    (net (code "89") (name "unconnected-(IC1-CPD2-Pad119)") (class "Default")
      (node (ref "IC1") (pin "119") (pinfunction "CPD2_119") (pintype "passive+no_connect"))
    )
    (net (code "90") (name "unconnected-(IC1-CPD3-Pad118)") (class "Default")
      (node (ref "IC1") (pin "118") (pinfunction "CPD3_118") (pintype "passive+no_connect"))
    )
    (net (code "91") (name "unconnected-(IC1-CPD4-Pad117)") (class "Default")
      (node (ref "IC1") (pin "117") (pinfunction "CPD4_117") (pintype "passive+no_connect"))
    )
    (net (code "92") (name "unconnected-(IC1-CPD5-Pad115)") (class "Default")
      (node (ref "IC1") (pin "115") (pinfunction "CPD5_115") (pintype "passive+no_connect"))
    )
    (net (code "93") (name "unconnected-(IC1-CPD6-Pad114)") (class "Default")
      (node (ref "IC1") (pin "114") (pinfunction "CPD6_114") (pintype "passive+no_connect"))
    )
    (net (code "94") (name "unconnected-(IC1-CPD7-Pad112)") (class "Default")
      (node (ref "IC1") (pin "112") (pinfunction "CPD7_112") (pintype "passive+no_connect"))
    )
    (net (code "95") (name "unconnected-(IC1-CPD8-Pad111)") (class "Default")
      (node (ref "IC1") (pin "111") (pinfunction "CPD8_111") (pintype "passive+no_connect"))
    )
    (net (code "96") (name "unconnected-(IC1-CPD9-Pad110)") (class "Default")
      (node (ref "IC1") (pin "110") (pinfunction "CPD9_110") (pintype "passive+no_connect"))
    )
    (net (code "97") (name "unconnected-(IC1-CPD10-Pad109)") (class "Default")
      (node (ref "IC1") (pin "109") (pinfunction "CPD10_109") (pintype "passive+no_connect"))
    )
    (net (code "98") (name "unconnected-(IC1-CPD11-Pad108)") (class "Default")
      (node (ref "IC1") (pin "108") (pinfunction "CPD11_108") (pintype "passive+no_connect"))
    )
    (net (code "99") (name "unconnected-(IC1-CPD12-Pad106)") (class "Default")
      (node (ref "IC1") (pin "106") (pinfunction "CPD12_106") (pintype "passive+no_connect"))
    )
    (net (code "100") (name "unconnected-(IC1-CPD13-Pad105)") (class "Default")
      (node (ref "IC1") (pin "105") (pinfunction "CPD13_105") (pintype "passive+no_connect"))
    )
    (net (code "101") (name "unconnected-(IC1-CPD14-Pad104)") (class "Default")
      (node (ref "IC1") (pin "104") (pinfunction "CPD14_104") (pintype "passive+no_connect"))
    )
    (net (code "102") (name "unconnected-(IC1-CPD15-Pad99)") (class "Default")
      (node (ref "IC1") (pin "99") (pinfunction "CPD15_99") (pintype "passive+no_connect"))
    )
    (net (code "103") (name "unconnected-(IC1-CPD15-Pad101)") (class "Default")
      (node (ref "IC1") (pin "101") (pinfunction "CPD15_101") (pintype "passive+no_connect"))
    )
    (net (code "104") (name "unconnected-(IC1-CPD16-Pad100)") (class "Default")
      (node (ref "IC1") (pin "100") (pinfunction "CPD16_100") (pintype "passive+no_connect"))
    )
    (net (code "105") (name "unconnected-(IC1-CPD18-Pad98)") (class "Default")
      (node (ref "IC1") (pin "98") (pinfunction "CPD18_98") (pintype "passive+no_connect"))
    )
    (net (code "106") (name "unconnected-(IC1-CPD19-Pad97)") (class "Default")
      (node (ref "IC1") (pin "97") (pinfunction "CPD19_97") (pintype "passive+no_connect"))
    )
    (net (code "107") (name "unconnected-(IC1-CPD20-Pad96)") (class "Default")
      (node (ref "IC1") (pin "96") (pinfunction "CPD20_96") (pintype "passive+no_connect"))
    )
    (net (code "108") (name "unconnected-(IC1-CPD21-Pad95)") (class "Default")
      (node (ref "IC1") (pin "95") (pinfunction "CPD21_95") (pintype "passive+no_connect"))
    )
    (net (code "109") (name "unconnected-(IC1-CPD22-Pad93)") (class "Default")
      (node (ref "IC1") (pin "93") (pinfunction "CPD22_93") (pintype "passive+no_connect"))
    )
    (net (code "110") (name "unconnected-(IC1-CPD23-Pad92)") (class "Default")
      (node (ref "IC1") (pin "92") (pinfunction "CPD23_92") (pintype "passive+no_connect"))
    )
    (net (code "111") (name "unconnected-(IC1-CPD24-Pad91)") (class "Default")
      (node (ref "IC1") (pin "91") (pinfunction "CPD24_91") (pintype "passive+no_connect"))
    )
    (net (code "112") (name "unconnected-(IC1-CPD25-Pad89)") (class "Default")
      (node (ref "IC1") (pin "89") (pinfunction "CPD25_89") (pintype "passive+no_connect"))
    )
    (net (code "113") (name "unconnected-(IC1-CPD26-Pad85)") (class "Default")
      (node (ref "IC1") (pin "85") (pinfunction "CPD26_85") (pintype "passive+no_connect"))
    )
    (net (code "114") (name "unconnected-(IC1-CPD27-Pad84)") (class "Default")
      (node (ref "IC1") (pin "84") (pinfunction "CPD27_84") (pintype "passive+no_connect"))
    )
    (net (code "115") (name "unconnected-(IC1-CPD28-Pad83)") (class "Default")
      (node (ref "IC1") (pin "83") (pinfunction "CPD28_83") (pintype "passive+no_connect"))
    )
    (net (code "116") (name "unconnected-(IC1-CPD29-Pad82)") (class "Default")
      (node (ref "IC1") (pin "82") (pinfunction "CPD29_82") (pintype "passive+no_connect"))
    )
    (net (code "117") (name "unconnected-(IC1-CPD30-Pad81)") (class "Default")
      (node (ref "IC1") (pin "81") (pinfunction "CPD30_81") (pintype "passive+no_connect"))
    )
    (net (code "118") (name "unconnected-(IC1-CPD31-Pad79)") (class "Default")
      (node (ref "IC1") (pin "79") (pinfunction "CPD31_79") (pintype "passive+no_connect"))
    )
    (net (code "119") (name "unconnected-(IC1-CPE-Pad75)") (class "Default")
      (node (ref "IC1") (pin "75") (pinfunction "CPE_75") (pintype "passive+no_connect"))
    )
    (net (code "120") (name "unconnected-(IC1-CPSPV-Pad71)") (class "Default")
      (node (ref "IC1") (pin "71") (pinfunction "CPSPV_71") (pintype "passive+no_connect"))
    )
    (net (code "121") (name "unconnected-(IC1-LINE-Pad10)") (class "Default")
      (node (ref "IC1") (pin "10") (pinfunction "LINE_10") (pintype "passive+no_connect"))
    )
    (net (code "122") (name "unconnected-(IC1-LOCK-Pad11)") (class "Default")
      (node (ref "IC1") (pin "11") (pinfunction "LOCK_11") (pintype "passive+no_connect"))
    )
    (net (code "123") (name "unconnected-(IC1-MSE-Pad19)") (class "Default")
      (node (ref "IC1") (pin "19") (pinfunction "MSE_19") (pintype "passive+no_connect"))
    )
    (net (code "124") (name "unconnected-(IC1-NC-Pad8)") (class "Default")
      (node (ref "IC1") (pin "8") (pinfunction "NC_8") (pintype "passive+no_connect"))
    )
    (net (code "125") (name "unconnected-(IC1-NC-Pad14)") (class "Default")
      (node (ref "IC1") (pin "14") (pinfunction "NC_14") (pintype "passive+no_connect"))
    )
    (net (code "126") (name "unconnected-(IC1-NC-Pad27)") (class "Default")
      (node (ref "IC1") (pin "27") (pinfunction "NC_27") (pintype "passive+no_connect"))
    )
    (net (code "127") (name "unconnected-(IC1-NC-Pad33)") (class "Default")
      (node (ref "IC1") (pin "33") (pinfunction "NC_33") (pintype "passive+no_connect"))
    )
    (net (code "128") (name "unconnected-(IC1-NC-Pad48)") (class "Default")
      (node (ref "IC1") (pin "48") (pinfunction "NC_48") (pintype "passive+no_connect"))
    )
    (net (code "129") (name "unconnected-(IC1-NC-Pad54)") (class "Default")
      (node (ref "IC1") (pin "54") (pinfunction "NC_54") (pintype "passive+no_connect"))
    )
    (net (code "130") (name "unconnected-(IC1-NC-Pad67)") (class "Default")
      (node (ref "IC1") (pin "67") (pinfunction "NC_67") (pintype "passive+no_connect"))
    )
    (net (code "131") (name "unconnected-(IC1-NC-Pad73)") (class "Default")
      (node (ref "IC1") (pin "73") (pinfunction "NC_73") (pintype "passive+no_connect"))
    )
    (net (code "132") (name "unconnected-(IC1-NC-Pad88)") (class "Default")
      (node (ref "IC1") (pin "88") (pinfunction "NC_88") (pintype "passive+no_connect"))
    )
    (net (code "133") (name "unconnected-(IC1-NC-Pad94)") (class "Default")
      (node (ref "IC1") (pin "94") (pinfunction "NC_94") (pintype "passive+no_connect"))
    )
    (net (code "134") (name "unconnected-(IC1-NC-Pad107)") (class "Default")
      (node (ref "IC1") (pin "107") (pinfunction "NC_107") (pintype "passive+no_connect"))
    )
    (net (code "135") (name "unconnected-(IC1-NC-Pad113)") (class "Default")
      (node (ref "IC1") (pin "113") (pinfunction "NC_113") (pintype "passive+no_connect"))
    )
    (net (code "136") (name "unconnected-(IC1-NC-Pad128)") (class "Default")
      (node (ref "IC1") (pin "128") (pinfunction "NC_128") (pintype "passive+no_connect"))
    )
    (net (code "137") (name "unconnected-(IC1-NC-Pad134)") (class "Default")
      (node (ref "IC1") (pin "134") (pinfunction "NC_134") (pintype "passive+no_connect"))
    )
    (net (code "138") (name "unconnected-(IC1-NC-Pad147)") (class "Default")
      (node (ref "IC1") (pin "147") (pinfunction "NC_147") (pintype "passive+no_connect"))
    )
    (net (code "139") (name "unconnected-(IC1-NC-Pad153)") (class "Default")
      (node (ref "IC1") (pin "153") (pinfunction "NC_153") (pintype "passive+no_connect"))
    )
    (net (code "140") (name "unconnected-(IC1-{slash}CPI-Pad72)") (class "Default")
      (node (ref "IC1") (pin "72") (pinfunction "/CPI_72") (pintype "passive+no_connect"))
    )
    (net (code "141") (name "unconnected-(IC1-{slash}OPC-Pad74)") (class "Default")
      (node (ref "IC1") (pin "74") (pinfunction "/OPC_74") (pintype "passive+no_connect"))
    )
    (net (code "142") (name "unconnected-(IC1-{slash}TEST-Pad35)") (class "Default")
      (node (ref "IC1") (pin "35") (pinfunction "/TEST_35") (pintype "passive+no_connect"))
    )
    (net (code "143") (name "unconnected-(IC1-{slash}WAIT-Pad34)") (class "Default")
      (node (ref "IC1") (pin "34") (pinfunction "/WAIT_34") (pintype "passive+no_connect"))
    )
    (net (code "144") (name "unconnected-(IC2-2Q-Pad9)") (class "Default")
      (node (ref "IC2") (pin "9") (pinfunction "2Q_9") (pintype "passive+no_connect"))
    )
    (net (code "145") (name "unconnected-(PL1-CPA-Pad76)") (class "Default")
      (node (ref "PL1") (pin "76") (pinfunction "CPA_76") (pintype "passive+no_connect"))
    )
    (net (code "146") (name "unconnected-(PL1-CPB-Pad12)") (class "Default")
      (node (ref "PL1") (pin "12") (pinfunction "CPB_12") (pintype "passive+no_connect"))
    )
    (net (code "147") (name "unconnected-(PL1-PHI1-Pad2)") (class "Default")
      (node (ref "PL1") (pin "2") (pinfunction "PHI1_2") (pintype "passive+no_connect"))
    )
    (net (code "148") (name "unconnected-(PL1-{slash}OPC-Pad4)") (class "Default")
      (node (ref "PL1") (pin "4") (pinfunction "/OPC_4") (pintype "passive+no_connect"))
    )
    (net (code "149") (name "unconnected-(X1-Pad1)") (class "Default")
      (node (ref "X1") (pin "1") (pinfunction "1_1") (pintype "passive+no_connect"))
    )
  )
)
